# DAC.net
KiCad netlist of a schematic drawn in Altium Designer
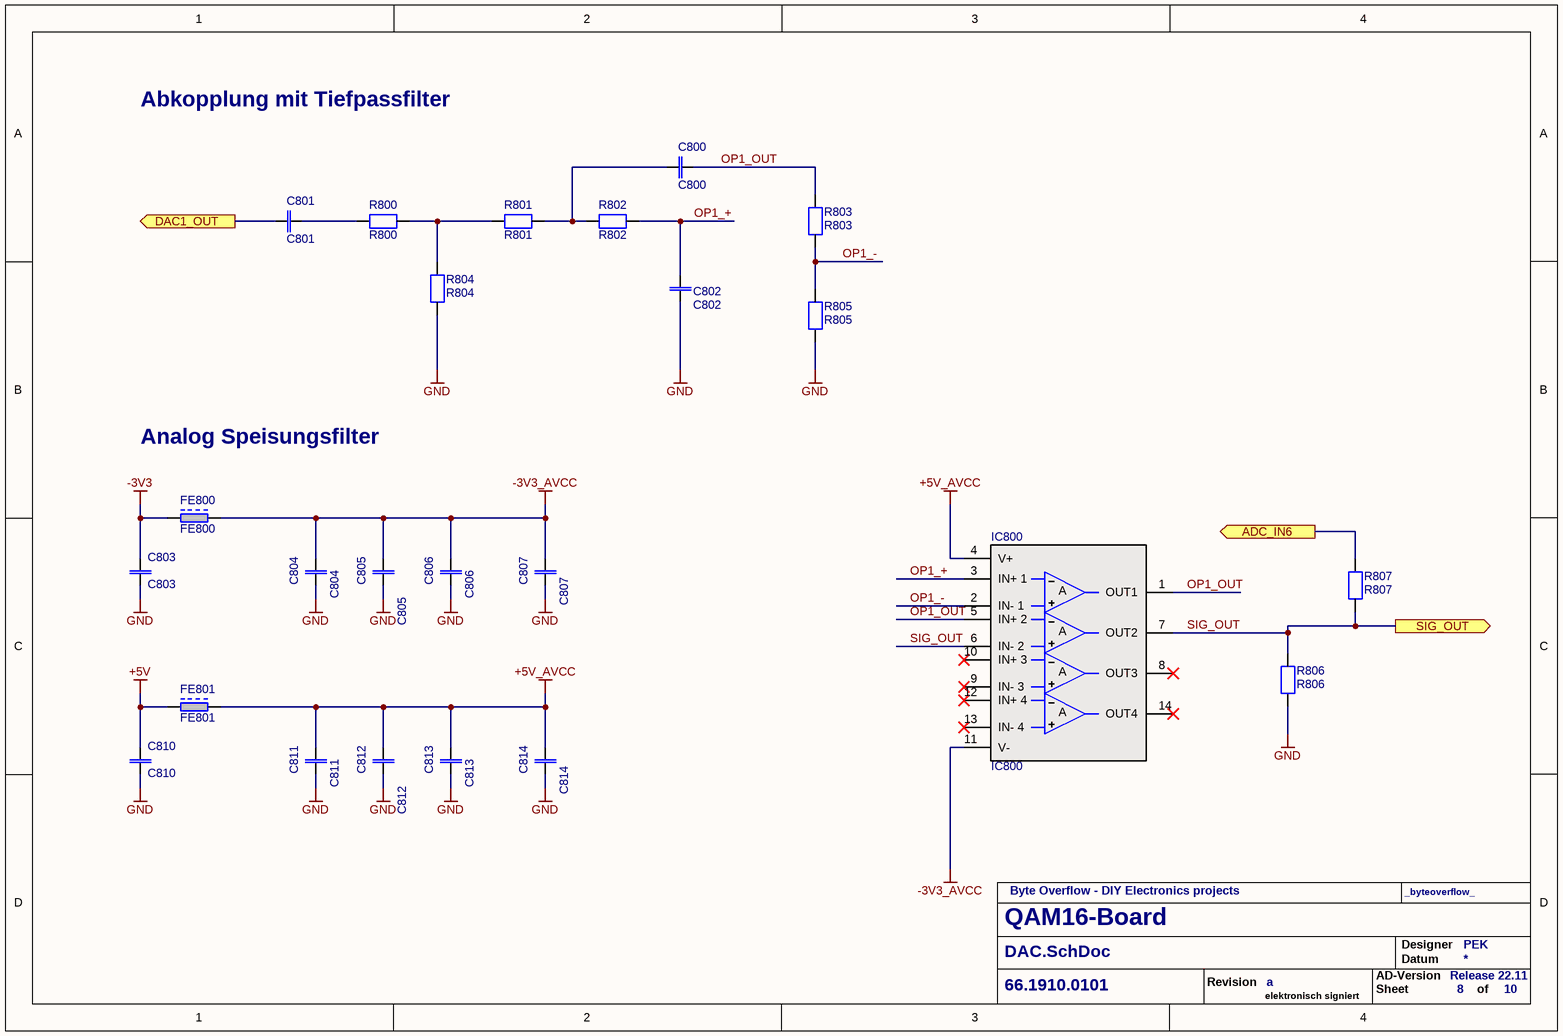
[diagram p0: DAC.SchDoc]

(export (version "E")
  (design (tool "Eeschema 10.0.6"))
  (components
    (comp (ref "C800")
      (value "C 220nF 16V")
      (footprint "0603-1608")
      (description "Capacitor")
      (fields
        (field (name "MANUFACTURER") "KEMET")
        (field (name "MANUFACTURER PART NUMBER") "C0603C224K4RAC7867")
        (field (name "VERIFICATION") "05.07.2012 OPT")
      )
      (libsource (lib "Database_Libs1") (part "Kondensator"))
    )
    (comp (ref "C801")
      (value "C 1uF 50V")
      (footprint "0805-2012")
      (description "Capacitor")
      (fields
        (field (name "MANUFACTURER") "Murata Electronics North America")
        (field (name "MANUFACTURER PART NUMBER") "GRM21BF51H105ZA12L")
      )
      (libsource (lib "Database_Libs1") (part "Kondensator"))
    )
    (comp (ref "C802")
      (value "C 220nF 16V")
      (footprint "0603-1608")
      (description "Capacitor")
      (fields
        (field (name "MANUFACTURER") "KEMET")
        (field (name "MANUFACTURER PART NUMBER") "C0603C224K4RAC7867")
        (field (name "VERIFICATION") "05.07.2012 OPT")
      )
      (libsource (lib "Database_Libs1") (part "Kondensator"))
    )
    (comp (ref "C803")
      (value "C 4.7uF 6.3V")
      (footprint "0402-1005")
      (description "Capacitor")
      (fields
        (field (name "MANUFACTURER") "Taiyo Yuden")
        (field (name "MANUFACTURER PART NUMBER") "JMK105BBJ475MV-F")
        (field (name "VERIFICATION") "05.07.2012 OPT")
      )
      (libsource (lib "Database_Libs1") (part "Kondensator"))
    )
    (comp (ref "C804")
      (value "C 1uF 50V")
      (footprint "0805-2012")
      (description "Capacitor")
      (fields
        (field (name "MANUFACTURER") "Murata Electronics North America")
        (field (name "MANUFACTURER PART NUMBER") "GRM21BF51H105ZA12L")
      )
      (libsource (lib "Database_Libs1") (part "Kondensator"))
    )
    (comp (ref "C805")
      (value "C 100nF 50V X7R")
      (footprint "0603-1608")
      (description "Capacitor")
      (fields
        (field (name "MANUFACTURER") "KEMET")
        (field (name "MANUFACTURER PART NUMBER") "C0603C104K5RACTU")
      )
      (libsource (lib "Database_Libs1") (part "Kondensator"))
    )
    (comp (ref "C806")
      (value "C 1uF 50V")
      (footprint "0805-2012")
      (description "Capacitor")
      (fields
        (field (name "MANUFACTURER") "Murata Electronics North America")
        (field (name "MANUFACTURER PART NUMBER") "GRM21BF51H105ZA12L")
      )
      (libsource (lib "Database_Libs1") (part "Kondensator"))
    )
    (comp (ref "C807")
      (value "C 100nF 50V X7R")
      (footprint "0603-1608")
      (description "Capacitor")
      (fields
        (field (name "MANUFACTURER") "KEMET")
        (field (name "MANUFACTURER PART NUMBER") "C0603C104K5RACTU")
      )
      (libsource (lib "Database_Libs1") (part "Kondensator"))
    )
    (comp (ref "C810")
      (value "C 4.7uF 6.3V")
      (footprint "0402-1005")
      (description "Capacitor")
      (fields
        (field (name "MANUFACTURER") "Taiyo Yuden")
        (field (name "MANUFACTURER PART NUMBER") "JMK105BBJ475MV-F")
        (field (name "VERIFICATION") "05.07.2012 OPT")
      )
      (libsource (lib "Database_Libs1") (part "Kondensator"))
    )
    (comp (ref "C811")
      (value "C 1uF 50V")
      (footprint "0805-2012")
      (description "Capacitor")
      (fields
        (field (name "MANUFACTURER") "Murata Electronics North America")
        (field (name "MANUFACTURER PART NUMBER") "GRM21BF51H105ZA12L")
      )
      (libsource (lib "Database_Libs1") (part "Kondensator"))
    )
    (comp (ref "C812")
      (value "C 100nF 50V X7R")
      (footprint "0603-1608")
      (description "Capacitor")
      (fields
        (field (name "MANUFACTURER") "KEMET")
        (field (name "MANUFACTURER PART NUMBER") "C0603C104K5RACTU")
      )
      (libsource (lib "Database_Libs1") (part "Kondensator"))
    )
    (comp (ref "C813")
      (value "C 1uF 50V")
      (footprint "0805-2012")
      (description "Capacitor")
      (fields
        (field (name "MANUFACTURER") "Murata Electronics North America")
        (field (name "MANUFACTURER PART NUMBER") "GRM21BF51H105ZA12L")
      )
      (libsource (lib "Database_Libs1") (part "Kondensator"))
    )
    (comp (ref "C814")
      (value "C 100nF 50V X7R")
      (footprint "0603-1608")
      (description "Capacitor")
      (fields
        (field (name "MANUFACTURER") "KEMET")
        (field (name "MANUFACTURER PART NUMBER") "C0603C104K5RACTU")
      )
      (libsource (lib "Database_Libs1") (part "Kondensator"))
    )
    (comp (ref "FE800")
      (value "BLM18AG102SN1D")
      (footprint "0603-1608")
      (description "Ferrite")
      (fields (field (name "MANUFACTURER") "Murata Electronics North America"))
      (libsource (lib "Database_Libs1") (part "Ferrit"))
    )
    (comp (ref "FE801")
      (value "BLM18AG102SN1D")
      (footprint "0603-1608")
      (description "Ferrite")
      (fields (field (name "MANUFACTURER") "Murata Electronics North America"))
      (libsource (lib "Database_Libs1") (part "Ferrit"))
    )
    (comp (ref "IC800")
      (value "LMC6484IMX/NOPB")
      (footprint "SOIC-14")
      (description "OPAMP")
      (fields (field (name "MANUFACTURER") "Texas Instruments"))
      (libsource (lib "Database_Libs1") (part "LMC6484"))
    )
    (comp (ref "R800")
      (value "R 56k 1%")
      (footprint "0603-1608")
      (description "Resistor")
      (fields
        (field (name "MANUFACTURER") "Vishay Dale")
        (field (name "MANUFACTURER PART NUMBER") "CRCW060356K0FKEA")
        (field (name "VERIFICATION") "05.07.2012 OPT")
      )
      (libsource (lib "Database_Libs1") (part "Resistor"))
    )
    (comp (ref "R801")
      (value "R 10k 1%")
      (footprint "0603-1608")
      (description "Resistor")
      (fields
        (field (name "MANUFACTURER") "Vishay Dale")
        (field (name "MANUFACTURER PART NUMBER") "CRCW060310K0FKEAHP")
        (field (name "VERIFICATION") "05.07.2012 OPT")
      )
      (libsource (lib "Database_Libs1") (part "Resistor"))
    )
    (comp (ref "R802")
      (value "R 10k 1%")
      (footprint "0603-1608")
      (description "Resistor")
      (fields
        (field (name "MANUFACTURER") "Vishay Dale")
        (field (name "MANUFACTURER PART NUMBER") "CRCW060310K0FKEAHP")
        (field (name "VERIFICATION") "05.07.2012 OPT")
      )
      (libsource (lib "Database_Libs1") (part "Resistor"))
    )
    (comp (ref "R803")
      (value "R 6.8k 1%")
      (footprint "0603-1608")
      (description "Resistor")
      (fields
        (field (name "MANUFACTURER") "Vishay Dale")
        (field (name "MANUFACTURER PART NUMBER") "CRCW06036K80FKEA")
        (field (name "VERIFICATION") "05.07.2012 OPT")
      )
      (libsource (lib "Database_Libs1") (part "Resistor"))
    )
    (comp (ref "R804")
      (value "R 18k 1%")
      (footprint "0603-1608")
      (description "Resistor")
      (fields
        (field (name "MANUFACTURER") "Vishay Dale")
        (field (name "MANUFACTURER PART NUMBER") "CRCW060318K0FKEA")
        (field (name "VERIFICATION") "05.07.2012 OPT")
      )
      (libsource (lib "Database_Libs1") (part "Resistor"))
    )
    (comp (ref "R805")
      (value "R 10k 1%")
      (footprint "0603-1608")
      (description "Resistor")
      (fields
        (field (name "MANUFACTURER") "Vishay Dale")
        (field (name "MANUFACTURER PART NUMBER") "CRCW060310K0FKEAHP")
        (field (name "VERIFICATION") "05.07.2012 OPT")
      )
      (libsource (lib "Database_Libs1") (part "Resistor"))
    )
    (comp (ref "R806")
      (value "R 10k 1%")
      (footprint "0603-1608")
      (description "Resistor")
      (fields
        (field (name "MANUFACTURER") "Vishay Dale")
        (field (name "MANUFACTURER PART NUMBER") "CRCW060310K0FKEAHP")
        (field (name "VERIFICATION") "05.07.2012 OPT")
      )
      (libsource (lib "Database_Libs1") (part "Resistor"))
    )
    (comp (ref "R807")
      (value "R 10k 1%")
      (footprint "0603-1608")
      (description "Resistor")
      (fields
        (field (name "MANUFACTURER") "Vishay Dale")
        (field (name "MANUFACTURER PART NUMBER") "CRCW060310K0FKEAHP")
        (field (name "VERIFICATION") "05.07.2012 OPT")
      )
      (libsource (lib "Database_Libs1") (part "Resistor"))
    )
  )
  (nets
    (net (code "1") (name "+5V") (class "Default")
      (node (ref "C810") (pin "1") (pinfunction "1_1") (pintype "passive"))
      (node (ref "FE801") (pin "2") (pintype "passive"))
    )
    (net (code "2") (name "+5V_AVCC") (class "Default")
      (node (ref "C811") (pin "1") (pinfunction "1_1") (pintype "passive"))
      (node (ref "C812") (pin "1") (pinfunction "1_1") (pintype "passive"))
      (node (ref "C813") (pin "1") (pinfunction "1_1") (pintype "passive"))
      (node (ref "C814") (pin "1") (pinfunction "1_1") (pintype "passive"))
      (node (ref "FE801") (pin "1") (pintype "passive"))
      (node (ref "IC800") (pin "4") (pinfunction "V+_4") (pintype "passive"))
    )
    (net (code "3") (name "-3V3") (class "Default")
      (node (ref "C803") (pin "1") (pinfunction "1_1") (pintype "passive"))
      (node (ref "FE800") (pin "2") (pintype "passive"))
    )
    (net (code "4") (name "-3V3_AVCC") (class "Default")
      (node (ref "C804") (pin "1") (pinfunction "1_1") (pintype "passive"))
      (node (ref "C805") (pin "1") (pinfunction "1_1") (pintype "passive"))
      (node (ref "C806") (pin "1") (pinfunction "1_1") (pintype "passive"))
      (node (ref "C807") (pin "1") (pinfunction "1_1") (pintype "passive"))
      (node (ref "FE800") (pin "1") (pintype "passive"))
      (node (ref "IC800") (pin "11") (pinfunction "V-_11") (pintype "passive"))
    )
    (net (code "5") (name "/ADC_IN6") (class "Default")
      (node (ref "R807") (pin "1") (pinfunction "1_1") (pintype "passive"))
    )
    (net (code "6") (name "/DAC1_OUT") (class "Default")
      (node (ref "C801") (pin "1") (pinfunction "1_1") (pintype "passive"))
    )
    (net (code "7") (name "/OP1_+") (class "Default")
      (node (ref "C802") (pin "2") (pinfunction "2_2") (pintype "passive"))
      (node (ref "IC800") (pin "3") (pinfunction "IN+_1_3") (pintype "passive"))
      (node (ref "R802") (pin "2") (pinfunction "2_2") (pintype "passive"))
    )
    (net (code "8") (name "/OP1_-") (class "Default")
      (node (ref "IC800") (pin "2") (pinfunction "IN-_1_2") (pintype "passive"))
      (node (ref "R803") (pin "2") (pinfunction "2_2") (pintype "passive"))
      (node (ref "R805") (pin "2") (pinfunction "2_2") (pintype "passive"))
    )
    (net (code "9") (name "/OP1_OUT") (class "Default")
      (node (ref "C800") (pin "2") (pinfunction "2_2") (pintype "passive"))
      (node (ref "IC800") (pin "1") (pinfunction "OUT1_1") (pintype "passive"))
      (node (ref "IC800") (pin "5") (pinfunction "IN+_2_5") (pintype "passive"))
      (node (ref "R803") (pin "1") (pinfunction "1_1") (pintype "passive"))
    )
    (net (code "10") (name "/SIG_OUT") (class "Default")
      (node (ref "IC800") (pin "6") (pinfunction "IN-_2_6") (pintype "passive"))
      (node (ref "IC800") (pin "7") (pinfunction "OUT2_7") (pintype "passive"))
      (node (ref "R806") (pin "2") (pinfunction "2_2") (pintype "passive"))
      (node (ref "R807") (pin "2") (pinfunction "2_2") (pintype "passive"))
    )
    (net (code "11") (name "GND") (class "Default")
      (node (ref "C802") (pin "1") (pinfunction "1_1") (pintype "passive"))
      (node (ref "C803") (pin "2") (pinfunction "2_2") (pintype "passive"))
      (node (ref "C804") (pin "2") (pinfunction "2_2") (pintype "passive"))
      (node (ref "C805") (pin "2") (pinfunction "2_2") (pintype "passive"))
      (node (ref "C806") (pin "2") (pinfunction "2_2") (pintype "passive"))
      (node (ref "C807") (pin "2") (pinfunction "2_2") (pintype "passive"))
      (node (ref "C810") (pin "2") (pinfunction "2_2") (pintype "passive"))
      (node (ref "C811") (pin "2") (pinfunction "2_2") (pintype "passive"))
      (node (ref "C812") (pin "2") (pinfunction "2_2") (pintype "passive"))
      (node (ref "C813") (pin "2") (pinfunction "2_2") (pintype "passive"))
      (node (ref "C814") (pin "2") (pinfunction "2_2") (pintype "passive"))
      (node (ref "R804") (pin "2") (pinfunction "2_2") (pintype "passive"))
      (node (ref "R805") (pin "1") (pinfunction "1_1") (pintype "passive"))
      (node (ref "R806") (pin "1") (pinfunction "1_1") (pintype "passive"))
    )
    (net (code "12") (name "Net-(C800-Pad1)") (class "Default")
      (node (ref "C800") (pin "1") (pinfunction "1_1") (pintype "passive"))
      (node (ref "R801") (pin "2") (pinfunction "2_2") (pintype "passive"))
      (node (ref "R802") (pin "1") (pinfunction "1_1") (pintype "passive"))
    )
    (net (code "13") (name "Net-(C801-Pad2)") (class "Default")
      (node (ref "C801") (pin "2") (pinfunction "2_2") (pintype "passive"))
      (node (ref "R800") (pin "1") (pinfunction "1_1") (pintype "passive"))
    )
    (net (code "14") (name "Net-(R800-Pad2)") (class "Default")
      (node (ref "R800") (pin "2") (pinfunction "2_2") (pintype "passive"))
      (node (ref "R801") (pin "1") (pinfunction "1_1") (pintype "passive"))
      (node (ref "R804") (pin "1") (pinfunction "1_1") (pintype "passive"))
    )
    (net (code "15") (name "unconnected-(IC800-IN+_3-Pad10)") (class "Default")
      (node (ref "IC800") (pin "10") (pinfunction "IN+_3_10") (pintype "passive+no_connect"))
    )
    (net (code "16") (name "unconnected-(IC800-IN+_4-Pad12)") (class "Default")
      (node (ref "IC800") (pin "12") (pinfunction "IN+_4_12") (pintype "passive+no_connect"))
    )
    (net (code "17") (name "unconnected-(IC800-IN-_3-Pad9)") (class "Default")
      (node (ref "IC800") (pin "9") (pinfunction "IN-_3_9") (pintype "passive+no_connect"))
    )
    (net (code "18") (name "unconnected-(IC800-IN-_4-Pad13)") (class "Default")
      (node (ref "IC800") (pin "13") (pinfunction "IN-_4_13") (pintype "passive+no_connect"))
    )
    (net (code "19") (name "unconnected-(IC800-OUT3-Pad8)") (class "Default")
      (node (ref "IC800") (pin "8") (pinfunction "OUT3_8") (pintype "passive+no_connect"))
    )
    (net (code "20") (name "unconnected-(IC800-OUT4-Pad14)") (class "Default")
      (node (ref "IC800") (pin "14") (pinfunction "OUT4_14") (pintype "passive+no_connect"))
    )
  )
)
